# 701C_Power_Button.net
KiCad netlist of a schematic drawn in Altium Designer
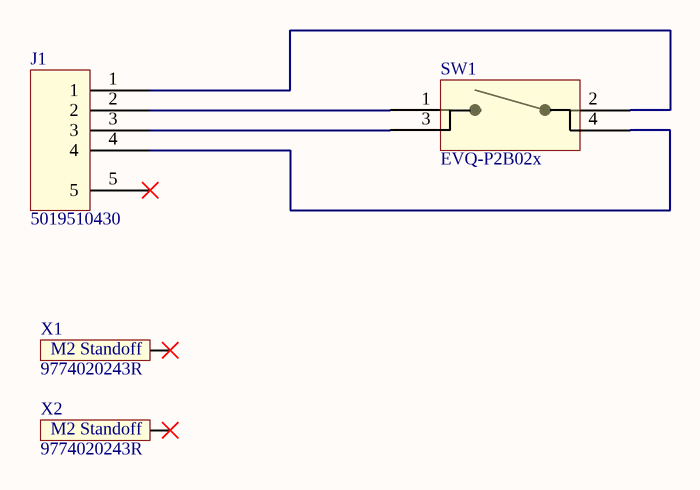
[diagram p0: 701C Power Button.SchDoc]

(export (version "E")
  (design (tool "Eeschema 10.0.6"))
  (components
    (comp (ref "J1")
      (value "5019510430")
      (footprint "5019510430")
      (description "4 Position FFC, FPC Connector Contacts, Vertical - 1 Sided 0.020\" (0.50mm) Surface Mount")
      (libsource (lib "KBuchka-IntLib") (part "5019510430"))
    )
    (comp (ref "SW1")
      (value "EVQ-P2B02x")
      (footprint "EVQ-P2B02x")
      (description "SWITCH TACTILE SPST-NO 0.02A 15V")
      (libsource (lib "KBuchka-IntLib") (part "EVQ-P2B02x"))
    )
    (comp (ref "X1")
      (value "9774020243R")
      (footprint "9774020243R")
      (libsource (lib "KBuchka-IntLib") (part "9774020243R"))
    )
    (comp (ref "X2")
      (value "9774020243R")
      (footprint "9774020243R")
      (libsource (lib "KBuchka-IntLib") (part "9774020243R"))
    )
  )
  (nets
    (net (code "1") (name "Net-(J1-Pad1)") (class "Default")
      (node (ref "J1") (pin "1") (pinfunction "1_1") (pintype "passive"))
      (node (ref "SW1") (pin "2") (pinfunction "2_2") (pintype "passive"))
    )
    (net (code "2") (name "Net-(J1-Pad2)") (class "Default")
      (node (ref "J1") (pin "2") (pinfunction "2_2") (pintype "passive"))
      (node (ref "SW1") (pin "1") (pinfunction "1_1") (pintype "passive"))
    )
    (net (code "3") (name "Net-(J1-Pad3)") (class "Default")
      (node (ref "J1") (pin "3") (pinfunction "3_3") (pintype "passive"))
      (node (ref "SW1") (pin "3") (pinfunction "3_3") (pintype "passive"))
    )
    (net (code "4") (name "Net-(J1-Pad4)") (class "Default")
      (node (ref "J1") (pin "4") (pinfunction "4_4") (pintype "passive"))
      (node (ref "SW1") (pin "4") (pinfunction "4_4") (pintype "passive"))
    )
    (net (code "5") (name "unconnected-(J1-Pad5)") (class "Default")
      (node (ref "J1") (pin "5") (pinfunction "5_5") (pintype "passive+no_connect"))
    )
    (net (code "6") (name "unconnected-(X1-Pad1)") (class "Default")
      (node (ref "X1") (pin "1") (pinfunction "1_1") (pintype "passive+no_connect"))
    )
    (net (code "7") (name "unconnected-(X2-Pad1)") (class "Default")
      (node (ref "X2") (pin "1") (pinfunction "1_1") (pintype "passive+no_connect"))
    )
  )
)
